# mic_amp.net
KiCad netlist of a schematic drawn in Altium Designer
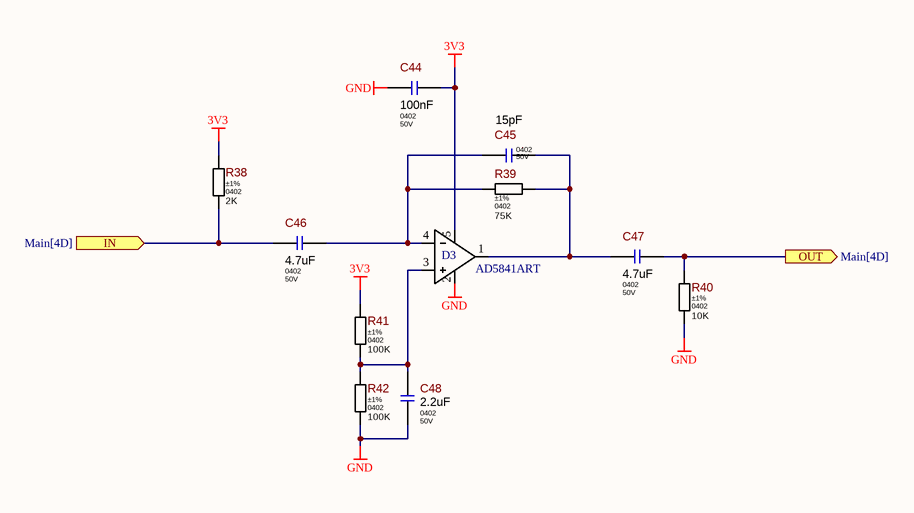
[diagram p0: mic_amp.SchDoc]

(export (version "E")
  (design (tool "Eeschema 10.0.6"))
  (components
    (comp (ref "C44")
      (value "100nF")
      (footprint "Cap_0402")
      (description "100nF 50V  ±25% 0402 Ceramic Capacitor")
      (fields
        (field (name "TOLERANCE") "±25%")
        (field (name "PACKAGE") "0402")
        (field (name "VOLTAGE") "50V")
      )
      (libsource (lib "Capacitors") (part "Cap_0402_100nF"))
    )
    (comp (ref "C45")
      (value "15pF")
      (footprint "Cap_0402")
      (description "15pF 50V  ±25% 0402 Ceramic Capacitor")
      (fields
        (field (name "TOLERANCE") "±25%")
        (field (name "PACKAGE") "0402")
        (field (name "VOLTAGE") "50V")
      )
      (libsource (lib "Capacitors") (part "Cap_0402_15pF"))
    )
    (comp (ref "C46")
      (value "4.7uF")
      (footprint "Cap_0402")
      (description "4.7uF 50V  ±25% 0402 Ceramic Capacitor")
      (fields
        (field (name "TOLERANCE") "±25%")
        (field (name "PACKAGE") "0402")
        (field (name "VOLTAGE") "50V")
      )
      (libsource (lib "Capacitors") (part "Cap_0402_4.7uF"))
    )
    (comp (ref "C47")
      (value "4.7uF")
      (footprint "Cap_0402")
      (description "4.7uF 50V  ±25% 0402 Ceramic Capacitor")
      (fields
        (field (name "TOLERANCE") "±25%")
        (field (name "PACKAGE") "0402")
        (field (name "VOLTAGE") "50V")
      )
      (libsource (lib "Capacitors") (part "Cap_0402_4.7uF"))
    )
    (comp (ref "C48")
      (value "2.2uF")
      (footprint "Cap_0402")
      (description "2.2uF 50V  ±25% 0402 Ceramic Capacitor")
      (fields
        (field (name "TOLERANCE") "±25%")
        (field (name "PACKAGE") "0402")
        (field (name "VOLTAGE") "50V")
      )
      (libsource (lib "Capacitors") (part "Cap_0402_2.2uF"))
    )
    (comp (ref "D3")
      (value "AD5841ART")
      (footprint "SOT-23-5")
      (description "CMOS Rail to Rail 1Mhz 2.7-5.5v")
      (libsource (lib "OpAmp") (part "AD5841ART"))
    )
    (comp (ref "R38")
      (value "2K")
      (footprint "Res_0402")
      (description "±1% 1/16W 0402")
      (fields
        (field (name "VOLTAGE") "50V")
        (field (name "TOLERANCE") "±1%")
        (field (name "PACKAGE") "0402")
        (field (name "Comment") "Res_0402_2K")
      )
      (libsource (lib "Resistors") (part "Res_0402_2K"))
    )
    (comp (ref "R39")
      (value "75K")
      (footprint "Res_0402")
      (description "±1% 1/16W 0402")
      (fields
        (field (name "VOLTAGE") "50V")
        (field (name "TOLERANCE") "±1%")
        (field (name "PACKAGE") "0402")
        (field (name "Comment") "Res_0402_75K")
      )
      (libsource (lib "Resistors") (part "Res_0402_75K"))
    )
    (comp (ref "R40")
      (value "10K")
      (footprint "Res_0402")
      (description "±1% 1/16W 0402")
      (fields
        (field (name "VOLTAGE") "50V")
        (field (name "TOLERANCE") "±1%")
        (field (name "PACKAGE") "0402")
        (field (name "Comment") "Res_0402_10K")
      )
      (libsource (lib "Resistors") (part "Res_0402_10K"))
    )
    (comp (ref "R41")
      (value "100K")
      (footprint "Res_0402")
      (description "±1% 1/16W 0402")
      (fields
        (field (name "VOLTAGE") "50V")
        (field (name "TOLERANCE") "±1%")
        (field (name "PACKAGE") "0402")
        (field (name "Comment") "Res_0402_100K")
      )
      (libsource (lib "Resistors") (part "Res_0402_100K"))
    )
    (comp (ref "R42")
      (value "100K")
      (footprint "Res_0402")
      (description "±1% 1/16W 0402")
      (fields
        (field (name "VOLTAGE") "50V")
        (field (name "TOLERANCE") "±1%")
        (field (name "PACKAGE") "0402")
        (field (name "Comment") "Res_0402_100K")
      )
      (libsource (lib "Resistors") (part "Res_0402_100K"))
    )
  )
  (nets
    (net (code "1") (name "/IN") (class "Default")
      (node (ref "C46") (pin "1") (pinfunction "1_1") (pintype "passive"))
      (node (ref "R38") (pin "2") (pintype "passive"))
    )
    (net (code "2") (name "/OUT") (class "Default")
      (node (ref "C47") (pin "2") (pinfunction "2_2") (pintype "passive"))
      (node (ref "R40") (pin "1") (pintype "passive"))
    )
    (net (code "3") (name "3V3") (class "Default")
      (node (ref "C44") (pin "2") (pinfunction "2_2") (pintype "passive"))
      (node (ref "D3") (pin "5") (pinfunction "5_5") (pintype "passive"))
      (node (ref "R38") (pin "1") (pintype "passive"))
      (node (ref "R41") (pin "1") (pintype "passive"))
    )
    (net (code "4") (name "GND") (class "Default")
      (node (ref "C44") (pin "1") (pinfunction "1_1") (pintype "passive"))
      (node (ref "C48") (pin "2") (pinfunction "2_2") (pintype "passive"))
      (node (ref "D3") (pin "2") (pinfunction "2_2") (pintype "passive"))
      (node (ref "R40") (pin "2") (pintype "passive"))
      (node (ref "R42") (pin "2") (pintype "passive"))
    )
    (net (code "5") (name "Net-(C45-Pad1)") (class "Default")
      (node (ref "C45") (pin "1") (pinfunction "1_1") (pintype "passive"))
      (node (ref "C46") (pin "2") (pinfunction "2_2") (pintype "passive"))
      (node (ref "D3") (pin "4") (pinfunction "4_4") (pintype "passive"))
      (node (ref "R39") (pin "1") (pintype "passive"))
    )
    (net (code "6") (name "Net-(C45-Pad2)") (class "Default")
      (node (ref "C45") (pin "2") (pinfunction "2_2") (pintype "passive"))
      (node (ref "C47") (pin "1") (pinfunction "1_1") (pintype "passive"))
      (node (ref "D3") (pin "1") (pinfunction "1_1") (pintype "passive"))
      (node (ref "R39") (pin "2") (pintype "passive"))
    )
    (net (code "7") (name "Net-(C48-Pad1)") (class "Default")
      (node (ref "C48") (pin "1") (pinfunction "1_1") (pintype "passive"))
      (node (ref "D3") (pin "3") (pinfunction "3_3") (pintype "passive"))
      (node (ref "R41") (pin "2") (pintype "passive"))
      (node (ref "R42") (pin "1") (pintype "passive"))
    )
  )
)
